# tranz.net
KiCad netlist of a schematic drawn in EAGLE
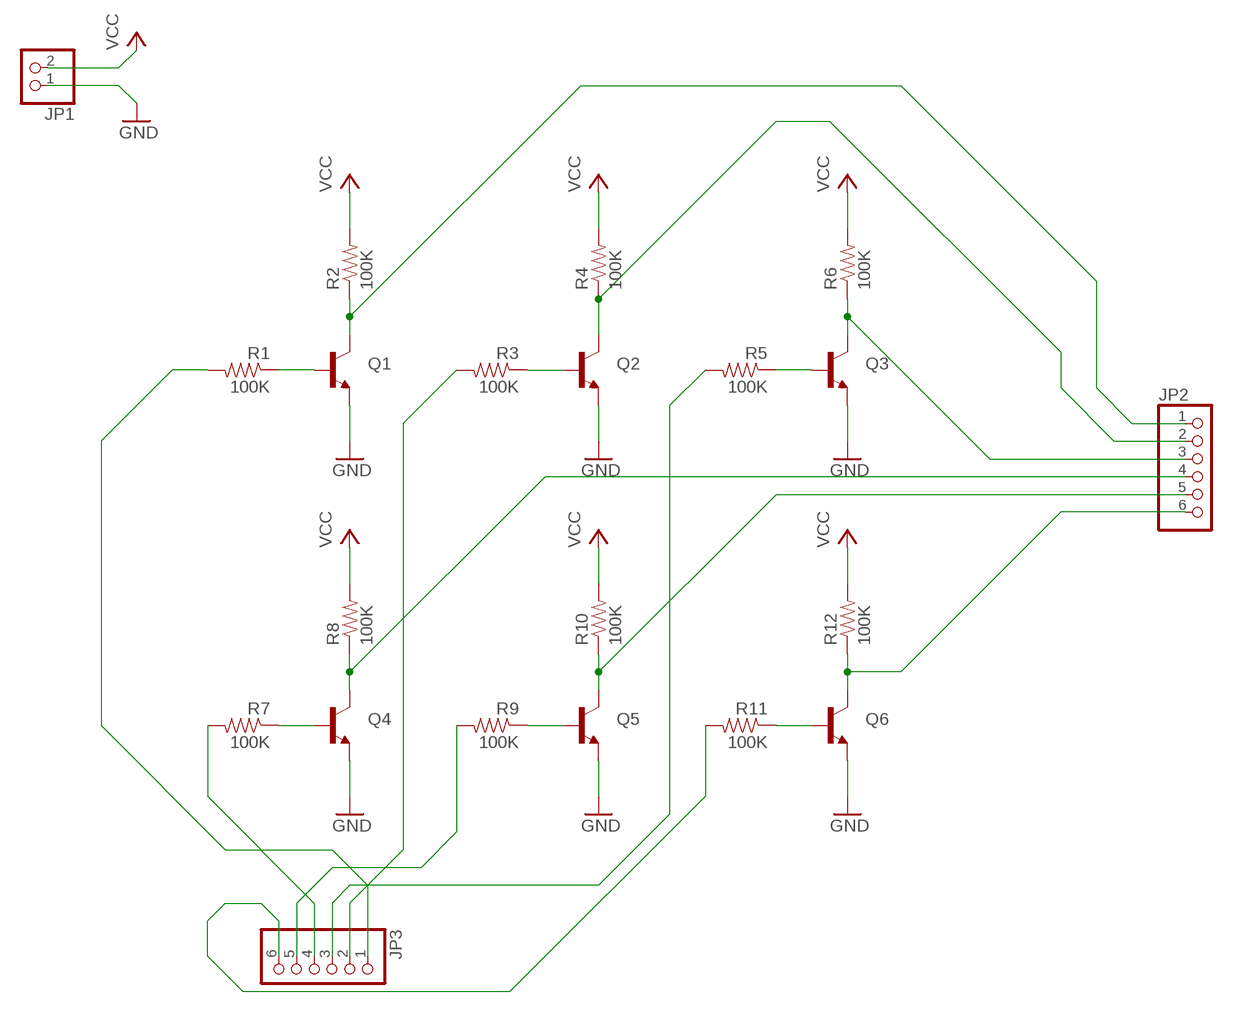
[diagram p0: schematic, sheet 1]

(export (version "E")
  (design (tool "Eeschema 10.0.6"))
  (components
    (comp (ref "JP1")
      (value "PINHD-1X2")
      (footprint "eagle-import:1X02")
      (libsource (lib "eagle-import") (part "PINHD-1X2"))
    )
    (comp (ref "JP2")
      (value "PINHD-1X6")
      (footprint "eagle-import:1X06")
      (libsource (lib "eagle-import") (part "PINHD-1X6"))
    )
    (comp (ref "JP3")
      (value "PINHD-1X6")
      (footprint "eagle-import:1X06")
      (libsource (lib "eagle-import") (part "PINHD-1X6"))
    )
    (comp (ref "Q1")
      (value "TRANSISTOR_NPN2N3904")
      (footprint "eagle-import:TO-92")
      (libsource (lib "eagle-import") (part "TRANSISTOR_NPN2N3904"))
    )
    (comp (ref "Q2")
      (value "TRANSISTOR_NPN2N3904")
      (footprint "eagle-import:TO-92")
      (libsource (lib "eagle-import") (part "TRANSISTOR_NPN2N3904"))
    )
    (comp (ref "Q3")
      (value "TRANSISTOR_NPN2N3904")
      (footprint "eagle-import:TO-92")
      (libsource (lib "eagle-import") (part "TRANSISTOR_NPN2N3904"))
    )
    (comp (ref "Q4")
      (value "TRANSISTOR_NPN2N3904")
      (footprint "eagle-import:TO-92")
      (libsource (lib "eagle-import") (part "TRANSISTOR_NPN2N3904"))
    )
    (comp (ref "Q5")
      (value "TRANSISTOR_NPN2N3904")
      (footprint "eagle-import:TO-92")
      (libsource (lib "eagle-import") (part "TRANSISTOR_NPN2N3904"))
    )
    (comp (ref "Q6")
      (value "TRANSISTOR_NPN2N3904")
      (footprint "eagle-import:TO-92")
      (libsource (lib "eagle-import") (part "TRANSISTOR_NPN2N3904"))
    )
    (comp (ref "R1")
      (value "100K")
      (footprint "eagle-import:1206")
      (libsource (lib "eagle-import") (part "RESISTOR1206"))
    )
    (comp (ref "R2")
      (value "100K")
      (footprint "eagle-import:1206")
      (libsource (lib "eagle-import") (part "RESISTOR1206"))
    )
    (comp (ref "R3")
      (value "100K")
      (footprint "eagle-import:1206")
      (libsource (lib "eagle-import") (part "RESISTOR1206"))
    )
    (comp (ref "R4")
      (value "100K")
      (footprint "eagle-import:1206")
      (libsource (lib "eagle-import") (part "RESISTOR1206"))
    )
    (comp (ref "R5")
      (value "100K")
      (footprint "eagle-import:1206")
      (libsource (lib "eagle-import") (part "RESISTOR1206"))
    )
    (comp (ref "R6")
      (value "100K")
      (footprint "eagle-import:1206")
      (libsource (lib "eagle-import") (part "RESISTOR1206"))
    )
    (comp (ref "R7")
      (value "100K")
      (footprint "eagle-import:1206")
      (libsource (lib "eagle-import") (part "RESISTOR1206"))
    )
    (comp (ref "R8")
      (value "100K")
      (footprint "eagle-import:1206")
      (libsource (lib "eagle-import") (part "RESISTOR1206"))
    )
    (comp (ref "R9")
      (value "100K")
      (footprint "eagle-import:1206")
      (libsource (lib "eagle-import") (part "RESISTOR1206"))
    )
    (comp (ref "R10")
      (value "100K")
      (footprint "eagle-import:1206")
      (libsource (lib "eagle-import") (part "RESISTOR1206"))
    )
    (comp (ref "R11")
      (value "100K")
      (footprint "eagle-import:1206")
      (libsource (lib "eagle-import") (part "RESISTOR1206"))
    )
    (comp (ref "R12")
      (value "100K")
      (footprint "eagle-import:1206")
      (libsource (lib "eagle-import") (part "RESISTOR1206"))
    )
  )
  (nets
    (net (code "1") (name "GND") (class "Default")
      (node (ref "JP1") (pin "1") (pinfunction "1_1") (pintype "passive"))
      (node (ref "Q1") (pin "1") (pinfunction "E_1") (pintype "passive"))
      (node (ref "Q2") (pin "1") (pinfunction "E_1") (pintype "passive"))
      (node (ref "Q3") (pin "1") (pinfunction "E_1") (pintype "passive"))
      (node (ref "Q4") (pin "1") (pinfunction "E_1") (pintype "passive"))
      (node (ref "Q5") (pin "1") (pinfunction "E_1") (pintype "passive"))
      (node (ref "Q6") (pin "1") (pinfunction "E_1") (pintype "passive"))
    )
    (net (code "2") (name "Net-(JP3-Pad1)") (class "Default")
      (node (ref "JP3") (pin "1") (pinfunction "1_1") (pintype "passive"))
      (node (ref "R1") (pin "2") (pinfunction "2_2") (pintype "passive"))
    )
    (net (code "3") (name "Net-(JP3-Pad2)") (class "Default")
      (node (ref "JP3") (pin "2") (pinfunction "2_2") (pintype "passive"))
      (node (ref "R3") (pin "2") (pinfunction "2_2") (pintype "passive"))
    )
    (net (code "4") (name "Net-(JP3-Pad3)") (class "Default")
      (node (ref "JP3") (pin "3") (pinfunction "3_3") (pintype "passive"))
      (node (ref "R5") (pin "2") (pinfunction "2_2") (pintype "passive"))
    )
    (net (code "5") (name "Net-(JP3-Pad4)") (class "Default")
      (node (ref "JP3") (pin "4") (pinfunction "4_4") (pintype "passive"))
      (node (ref "R7") (pin "2") (pinfunction "2_2") (pintype "passive"))
    )
    (net (code "6") (name "Net-(JP3-Pad5)") (class "Default")
      (node (ref "JP3") (pin "5") (pinfunction "5_5") (pintype "passive"))
      (node (ref "R9") (pin "2") (pinfunction "2_2") (pintype "passive"))
    )
    (net (code "7") (name "Net-(JP3-Pad6)") (class "Default")
      (node (ref "JP3") (pin "6") (pinfunction "6_6") (pintype "passive"))
      (node (ref "R11") (pin "2") (pinfunction "2_2") (pintype "passive"))
    )
    (net (code "8") (name "Net-(Q1-B)") (class "Default")
      (node (ref "Q1") (pin "2") (pinfunction "B_2") (pintype "passive"))
      (node (ref "R1") (pin "1") (pinfunction "1_1") (pintype "passive"))
    )
    (net (code "9") (name "Net-(Q1-C)") (class "Default")
      (node (ref "JP2") (pin "1") (pinfunction "1_1") (pintype "passive"))
      (node (ref "Q1") (pin "3") (pinfunction "C_3") (pintype "passive"))
      (node (ref "R2") (pin "1") (pinfunction "1_1") (pintype "passive"))
    )
    (net (code "10") (name "Net-(Q2-B)") (class "Default")
      (node (ref "Q2") (pin "2") (pinfunction "B_2") (pintype "passive"))
      (node (ref "R3") (pin "1") (pinfunction "1_1") (pintype "passive"))
    )
    (net (code "11") (name "Net-(Q2-C)") (class "Default")
      (node (ref "JP2") (pin "2") (pinfunction "2_2") (pintype "passive"))
      (node (ref "Q2") (pin "3") (pinfunction "C_3") (pintype "passive"))
      (node (ref "R4") (pin "1") (pinfunction "1_1") (pintype "passive"))
    )
    (net (code "12") (name "Net-(Q3-B)") (class "Default")
      (node (ref "Q3") (pin "2") (pinfunction "B_2") (pintype "passive"))
      (node (ref "R5") (pin "1") (pinfunction "1_1") (pintype "passive"))
    )
    (net (code "13") (name "Net-(Q3-C)") (class "Default")
      (node (ref "JP2") (pin "3") (pinfunction "3_3") (pintype "passive"))
      (node (ref "Q3") (pin "3") (pinfunction "C_3") (pintype "passive"))
      (node (ref "R6") (pin "1") (pinfunction "1_1") (pintype "passive"))
    )
    (net (code "14") (name "Net-(Q4-B)") (class "Default")
      (node (ref "Q4") (pin "2") (pinfunction "B_2") (pintype "passive"))
      (node (ref "R7") (pin "1") (pinfunction "1_1") (pintype "passive"))
    )
    (net (code "15") (name "Net-(Q4-C)") (class "Default")
      (node (ref "JP2") (pin "4") (pinfunction "4_4") (pintype "passive"))
      (node (ref "Q4") (pin "3") (pinfunction "C_3") (pintype "passive"))
      (node (ref "R8") (pin "1") (pinfunction "1_1") (pintype "passive"))
    )
    (net (code "16") (name "Net-(Q5-B)") (class "Default")
      (node (ref "Q5") (pin "2") (pinfunction "B_2") (pintype "passive"))
      (node (ref "R9") (pin "1") (pinfunction "1_1") (pintype "passive"))
    )
    (net (code "17") (name "Net-(Q5-C)") (class "Default")
      (node (ref "JP2") (pin "5") (pinfunction "5_5") (pintype "passive"))
      (node (ref "Q5") (pin "3") (pinfunction "C_3") (pintype "passive"))
      (node (ref "R10") (pin "1") (pinfunction "1_1") (pintype "passive"))
    )
    (net (code "18") (name "Net-(Q6-B)") (class "Default")
      (node (ref "Q6") (pin "2") (pinfunction "B_2") (pintype "passive"))
      (node (ref "R11") (pin "1") (pinfunction "1_1") (pintype "passive"))
    )
    (net (code "19") (name "Net-(Q6-C)") (class "Default")
      (node (ref "JP2") (pin "6") (pinfunction "6_6") (pintype "passive"))
      (node (ref "Q6") (pin "3") (pinfunction "C_3") (pintype "passive"))
      (node (ref "R12") (pin "1") (pinfunction "1_1") (pintype "passive"))
    )
    (net (code "20") (name "VCC") (class "Default")
      (node (ref "JP1") (pin "2") (pinfunction "2_2") (pintype "passive"))
      (node (ref "R10") (pin "2") (pinfunction "2_2") (pintype "passive"))
      (node (ref "R12") (pin "2") (pinfunction "2_2") (pintype "passive"))
      (node (ref "R2") (pin "2") (pinfunction "2_2") (pintype "passive"))
      (node (ref "R4") (pin "2") (pinfunction "2_2") (pintype "passive"))
      (node (ref "R6") (pin "2") (pinfunction "2_2") (pintype "passive"))
      (node (ref "R8") (pin "2") (pinfunction "2_2") (pintype "passive"))
    )
  )
)
